# freeDSP.net
KiCad netlist of a schematic drawn in EAGLE
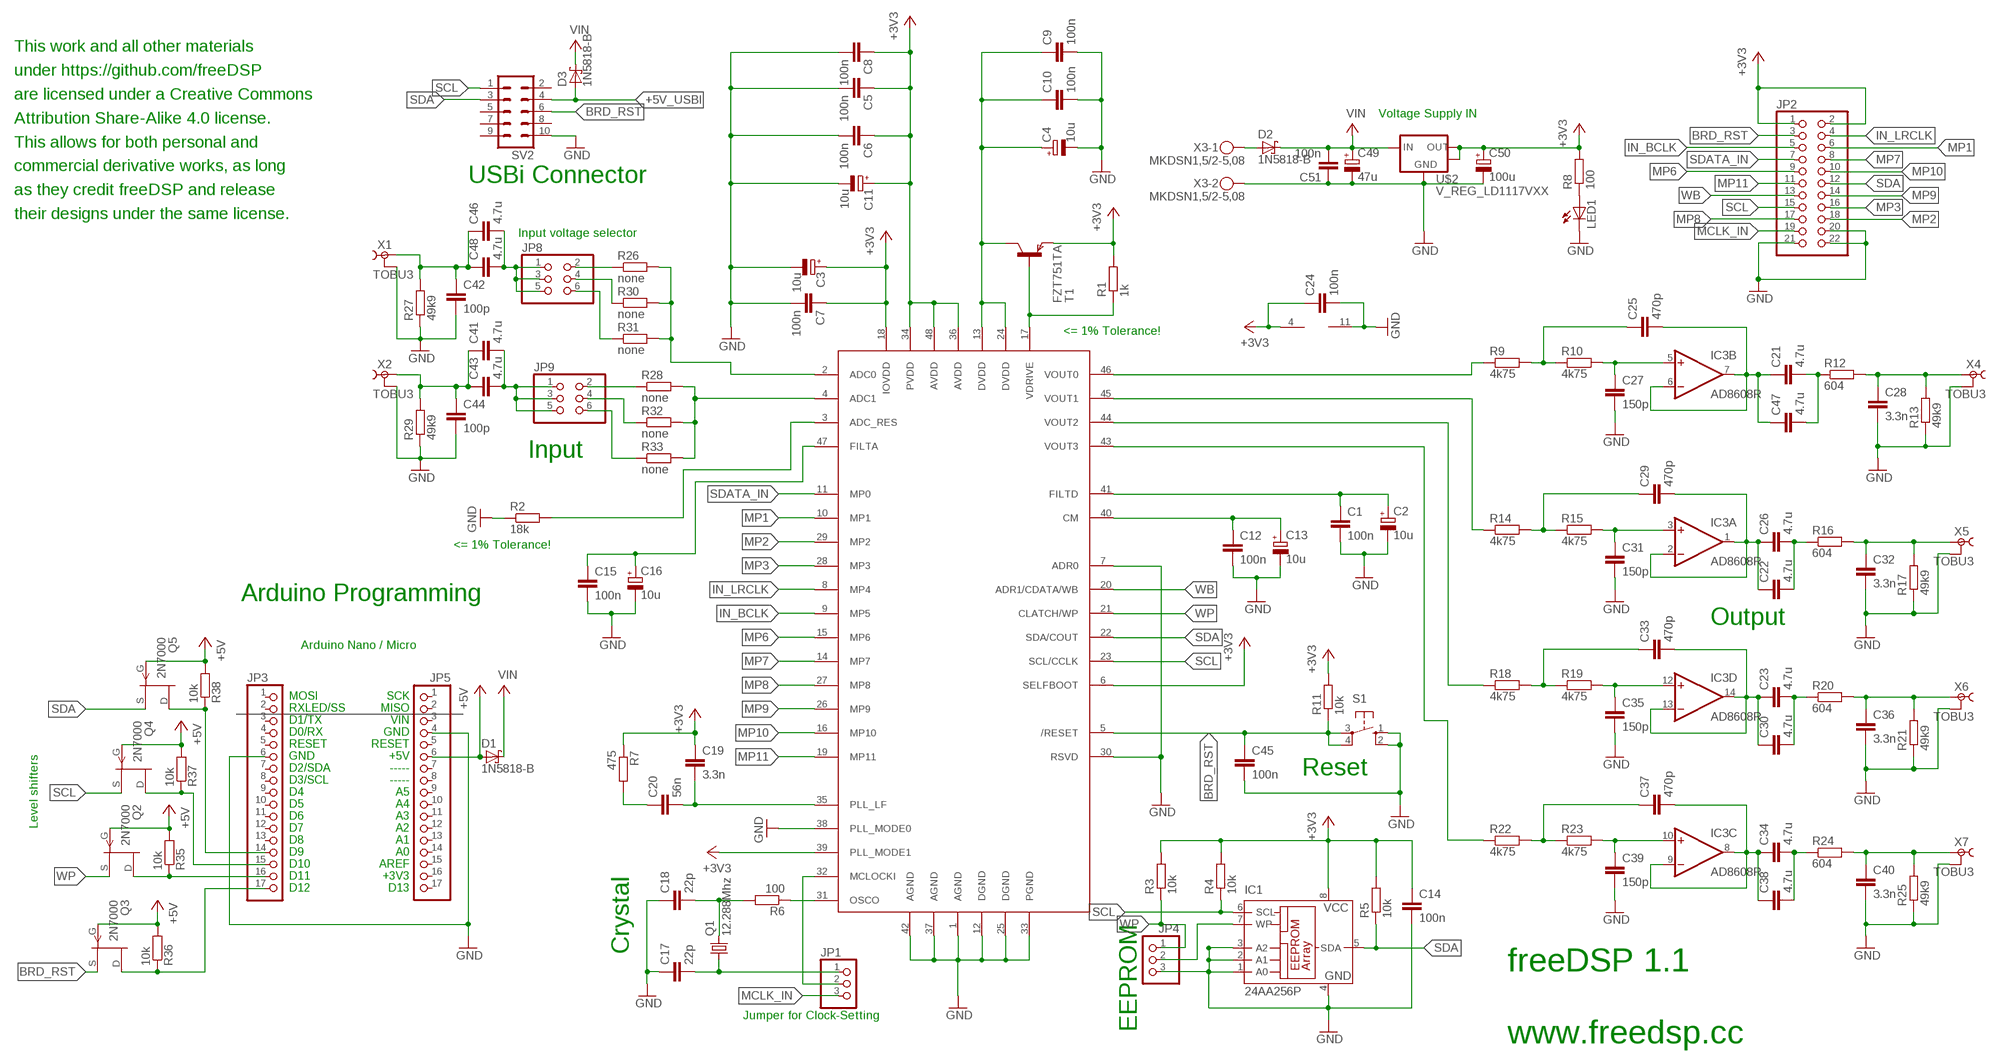
[diagram p0: schematic, sheet 1]

(export (version "E")
  (design (tool "Eeschema 10.0.6"))
  (components
    (comp (ref "C1")
      (value "100n")
      (footprint "eagle-import:C025-025X050")
      (libsource (lib "eagle-import") (part "C-EU025-025X050"))
    )
    (comp (ref "C2")
      (value "10u")
      (footprint "eagle-import:E1,8-4")
      (libsource (lib "eagle-import") (part "CPOL-EUE1.8-4"))
    )
    (comp (ref "C3")
      (value "10u")
      (footprint "eagle-import:E1,8-4")
      (libsource (lib "eagle-import") (part "CPOL-EUE1.8-4"))
    )
    (comp (ref "C4")
      (value "10u")
      (footprint "eagle-import:E1,8-4")
      (libsource (lib "eagle-import") (part "CPOL-EUE1.8-4"))
    )
    (comp (ref "C5")
      (value "100n")
      (footprint "eagle-import:C025-025X050")
      (libsource (lib "eagle-import") (part "C-EU025-025X050"))
    )
    (comp (ref "C6")
      (value "100n")
      (footprint "eagle-import:C025-025X050")
      (libsource (lib "eagle-import") (part "C-EU025-025X050"))
    )
    (comp (ref "C7")
      (value "100n")
      (footprint "eagle-import:C025-025X050")
      (libsource (lib "eagle-import") (part "C-EU025-025X050"))
    )
    (comp (ref "C8")
      (value "100n")
      (footprint "eagle-import:C025-025X050")
      (libsource (lib "eagle-import") (part "C-EU025-025X050"))
    )
    (comp (ref "C9")
      (value "100n")
      (footprint "eagle-import:C025-025X050")
      (libsource (lib "eagle-import") (part "C-EU025-025X050"))
    )
    (comp (ref "C10")
      (value "100n")
      (footprint "eagle-import:C025-025X050")
      (libsource (lib "eagle-import") (part "C-EU025-025X050"))
    )
    (comp (ref "C11")
      (value "10u")
      (footprint "eagle-import:E1,8-4")
      (libsource (lib "eagle-import") (part "CPOL-EUE1.8-4"))
    )
    (comp (ref "C12")
      (value "100n")
      (footprint "eagle-import:C025-025X050")
      (libsource (lib "eagle-import") (part "C-EU025-025X050"))
    )
    (comp (ref "C13")
      (value "10u")
      (footprint "eagle-import:E1,8-4")
      (libsource (lib "eagle-import") (part "CPOL-EUE1.8-4"))
    )
    (comp (ref "C14")
      (value "100n")
      (footprint "eagle-import:C025-025X050")
      (libsource (lib "eagle-import") (part "C-EU025-025X050"))
    )
    (comp (ref "C15")
      (value "100n")
      (footprint "eagle-import:C025-025X050")
      (libsource (lib "eagle-import") (part "C-EU025-025X050"))
    )
    (comp (ref "C16")
      (value "10u")
      (footprint "eagle-import:E1,8-4")
      (libsource (lib "eagle-import") (part "CPOL-EUE1.8-4"))
    )
    (comp (ref "C17")
      (value "22p")
      (footprint "eagle-import:C025-025X050")
      (libsource (lib "eagle-import") (part "C-EU025-025X050"))
    )
    (comp (ref "C18")
      (value "22p")
      (footprint "eagle-import:C025-025X050")
      (libsource (lib "eagle-import") (part "C-EU025-025X050"))
    )
    (comp (ref "C19")
      (value "3.3n")
      (footprint "eagle-import:C025-025X050")
      (libsource (lib "eagle-import") (part "C-EU025-025X050"))
    )
    (comp (ref "C20")
      (value "56n")
      (footprint "eagle-import:C025-025X050")
      (libsource (lib "eagle-import") (part "C-EU025-025X050"))
    )
    (comp (ref "C21")
      (value "4.7u")
      (footprint "eagle-import:C050-075X075")
      (libsource (lib "eagle-import") (part "C-EU050-075X075"))
    )
    (comp (ref "C22")
      (value "4.7u")
      (footprint "eagle-import:C050-075X075")
      (libsource (lib "eagle-import") (part "C-EU050-075X075"))
    )
    (comp (ref "C23")
      (value "4.7u")
      (footprint "eagle-import:C050-075X075")
      (libsource (lib "eagle-import") (part "C-EU050-075X075"))
    )
    (comp (ref "C24")
      (value "100n")
      (footprint "eagle-import:C025-025X050")
      (libsource (lib "eagle-import") (part "C-EU025-025X050"))
    )
    (comp (ref "C25")
      (value "470p")
      (footprint "eagle-import:C050-050X075")
      (libsource (lib "eagle-import") (part "C-EU050-050X075"))
    )
    (comp (ref "C26")
      (value "4.7u")
      (footprint "eagle-import:C050-075X075")
      (libsource (lib "eagle-import") (part "C-EU050-075X075"))
    )
    (comp (ref "C27")
      (value "150p")
      (footprint "eagle-import:C025-025X050")
      (libsource (lib "eagle-import") (part "C-EU025-025X050"))
    )
    (comp (ref "C28")
      (value "3.3n")
      (footprint "eagle-import:C025-025X050")
      (libsource (lib "eagle-import") (part "C-EU025-025X050"))
    )
    (comp (ref "C29")
      (value "470p")
      (footprint "eagle-import:C050-050X075")
      (libsource (lib "eagle-import") (part "C-EU050-050X075"))
    )
    (comp (ref "C30")
      (value "4.7u")
      (footprint "eagle-import:C050-075X075")
      (libsource (lib "eagle-import") (part "C-EU050-075X075"))
    )
    (comp (ref "C31")
      (value "150p")
      (footprint "eagle-import:C025-025X050")
      (libsource (lib "eagle-import") (part "C-EU025-025X050"))
    )
    (comp (ref "C32")
      (value "3.3n")
      (footprint "eagle-import:C025-025X050")
      (libsource (lib "eagle-import") (part "C-EU025-025X050"))
    )
    (comp (ref "C33")
      (value "470p")
      (footprint "eagle-import:C050-050X075")
      (libsource (lib "eagle-import") (part "C-EU050-050X075"))
    )
    (comp (ref "C34")
      (value "4.7u")
      (footprint "eagle-import:C050-075X075")
      (libsource (lib "eagle-import") (part "C-EU050-075X075"))
    )
    (comp (ref "C35")
      (value "150p")
      (footprint "eagle-import:C025-025X050")
      (libsource (lib "eagle-import") (part "C-EU025-025X050"))
    )
    (comp (ref "C36")
      (value "3.3n")
      (footprint "eagle-import:C025-025X050")
      (libsource (lib "eagle-import") (part "C-EU025-025X050"))
    )
    (comp (ref "C37")
      (value "470p")
      (footprint "eagle-import:C050-050X075")
      (libsource (lib "eagle-import") (part "C-EU050-050X075"))
    )
    (comp (ref "C38")
      (value "4.7u")
      (footprint "eagle-import:C050-075X075")
      (libsource (lib "eagle-import") (part "C-EU050-075X075"))
    )
    (comp (ref "C39")
      (value "150p")
      (footprint "eagle-import:C025-025X050")
      (libsource (lib "eagle-import") (part "C-EU025-025X050"))
    )
    (comp (ref "C40")
      (value "3.3n")
      (footprint "eagle-import:C025-025X050")
      (libsource (lib "eagle-import") (part "C-EU025-025X050"))
    )
    (comp (ref "C41")
      (value "4.7u")
      (footprint "eagle-import:C050-075X075")
      (libsource (lib "eagle-import") (part "C-EU050-075X075"))
    )
    (comp (ref "C42")
      (value "100p")
      (footprint "eagle-import:C025-025X050")
      (libsource (lib "eagle-import") (part "C-EU025-025X050"))
    )
    (comp (ref "C43")
      (value "4.7u")
      (footprint "eagle-import:C050-075X075")
      (libsource (lib "eagle-import") (part "C-EU050-075X075"))
    )
    (comp (ref "C44")
      (value "100p")
      (footprint "eagle-import:C025-025X050")
      (libsource (lib "eagle-import") (part "C-EU025-025X050"))
    )
    (comp (ref "C45")
      (value "100n")
      (footprint "eagle-import:C025-025X050")
      (libsource (lib "eagle-import") (part "C-EU025-025X050"))
    )
    (comp (ref "C46")
      (value "4.7u")
      (footprint "eagle-import:C050-075X075")
      (libsource (lib "eagle-import") (part "C-EU050-075X075"))
    )
    (comp (ref "C47")
      (value "4.7u")
      (footprint "eagle-import:C050-075X075")
      (libsource (lib "eagle-import") (part "C-EU050-075X075"))
    )
    (comp (ref "C48")
      (value "4.7u")
      (footprint "eagle-import:C050-075X075")
      (libsource (lib "eagle-import") (part "C-EU050-075X075"))
    )
    (comp (ref "C49")
      (value "47u")
      (footprint "eagle-import:E2,5-6")
      (libsource (lib "eagle-import") (part "CPOL-EUE2.5-6"))
    )
    (comp (ref "C50")
      (value "100u")
      (footprint "eagle-import:E2,5-6")
      (libsource (lib "eagle-import") (part "CPOL-EUE2.5-6"))
    )
    (comp (ref "C51")
      (value "100n")
      (footprint "eagle-import:C025-025X050")
      (libsource (lib "eagle-import") (part "C-EU025-025X050"))
    )
    (comp (ref "D1")
      (value "1N5818-B")
      (footprint "eagle-import:DO41-7.6")
      (libsource (lib "eagle-import") (part "1N5818-B"))
    )
    (comp (ref "D2")
      (value "1N5818-B")
      (footprint "eagle-import:DO41-7.6")
      (libsource (lib "eagle-import") (part "1N5818-B"))
    )
    (comp (ref "D3")
      (value "1N5818-B")
      (footprint "eagle-import:DO41-7.6")
      (libsource (lib "eagle-import") (part "1N5818-B"))
    )
    (comp (ref "IC1")
      (value "24AA256P")
      (footprint "eagle-import:DIL8")
      (fields (field (name "MF") "MICROCHIP") (field (name "MPN") "24AA256-I/P"))
      (libsource (lib "eagle-import") (part "24PAA256"))
    )
    (comp (ref "IC3")
      (value "AD8608R")
      (footprint "eagle-import:SO-14")
      (libsource (lib "eagle-import") (part "AD8608R"))
    )
    (comp (ref "JP1")
      (value "PINHD-1X3")
      (footprint "eagle-import:1X03")
      (libsource (lib "eagle-import") (part "PINHD-1X3"))
    )
    (comp (ref "JP2")
      (value "PINHD-2X11")
      (footprint "eagle-import:2X11")
      (libsource (lib "eagle-import") (part "PINHD-2X11"))
    )
    (comp (ref "JP3")
      (value "PINHD-1X17")
      (footprint "eagle-import:1X17")
      (libsource (lib "eagle-import") (part "PINHD-1X17"))
    )
    (comp (ref "JP4")
      (value "PINHD-1X3")
      (footprint "eagle-import:1X03")
      (libsource (lib "eagle-import") (part "PINHD-1X3"))
    )
    (comp (ref "JP5")
      (value "PINHD-1X17")
      (footprint "eagle-import:1X17")
      (libsource (lib "eagle-import") (part "PINHD-1X17"))
    )
    (comp (ref "JP8")
      (value "PINHD-2X3")
      (footprint "eagle-import:2X03")
      (libsource (lib "eagle-import") (part "PINHD-2X3"))
    )
    (comp (ref "JP9")
      (value "PINHD-2X3")
      (footprint "eagle-import:2X03")
      (libsource (lib "eagle-import") (part "PINHD-2X3"))
    )
    (comp (ref "LED1")
      (value "LED3MM")
      (footprint "eagle-import:LED3MM")
      (libsource (lib "eagle-import") (part "LED3MM"))
    )
    (comp (ref "Q1")
      (value "12.288Mhz")
      (footprint "eagle-import:HC49_S")
      (libsource (lib "eagle-import") (part "CRYSTALHC49S"))
    )
    (comp (ref "Q2")
      (value "2N7000")
      (footprint "eagle-import:TO92")
      (libsource (lib "eagle-import") (part "2N3819"))
    )
    (comp (ref "Q3")
      (value "2N7000")
      (footprint "eagle-import:TO92")
      (libsource (lib "eagle-import") (part "2N3819"))
    )
    (comp (ref "Q4")
      (value "2N7000")
      (footprint "eagle-import:TO92")
      (libsource (lib "eagle-import") (part "2N3819"))
    )
    (comp (ref "Q5")
      (value "2N7000")
      (footprint "eagle-import:TO92")
      (libsource (lib "eagle-import") (part "2N3819"))
    )
    (comp (ref "R1")
      (value "1k")
      (footprint "eagle-import:0207_10")
      (libsource (lib "eagle-import") (part "R-EU_0207/10"))
    )
    (comp (ref "R2")
      (value "18k")
      (footprint "eagle-import:0207_10")
      (libsource (lib "eagle-import") (part "R-EU_0207/10"))
    )
    (comp (ref "R3")
      (value "10k")
      (footprint "eagle-import:0207_10")
      (libsource (lib "eagle-import") (part "R-EU_0207/10"))
    )
    (comp (ref "R4")
      (value "10k")
      (footprint "eagle-import:0207_10")
      (libsource (lib "eagle-import") (part "R-EU_0207/10"))
    )
    (comp (ref "R5")
      (value "10k")
      (footprint "eagle-import:0207_10")
      (libsource (lib "eagle-import") (part "R-EU_0207/10"))
    )
    (comp (ref "R6")
      (value "100")
      (footprint "eagle-import:0207_10")
      (libsource (lib "eagle-import") (part "R-EU_0207/10"))
    )
    (comp (ref "R7")
      (value "475")
      (footprint "eagle-import:0207_10")
      (libsource (lib "eagle-import") (part "R-EU_0207/10"))
    )
    (comp (ref "R8")
      (value "100")
      (footprint "eagle-import:0207_10")
      (libsource (lib "eagle-import") (part "R-EU_0207/10"))
    )
    (comp (ref "R9")
      (value "4k75")
      (footprint "eagle-import:0207_10")
      (libsource (lib "eagle-import") (part "R-EU_0207/10"))
    )
    (comp (ref "R10")
      (value "4k75")
      (footprint "eagle-import:0207_10")
      (libsource (lib "eagle-import") (part "R-EU_0207/10"))
    )
    (comp (ref "R11")
      (value "10k")
      (footprint "eagle-import:0207_10")
      (libsource (lib "eagle-import") (part "R-EU_0207/10"))
    )
    (comp (ref "R12")
      (value "604")
      (footprint "eagle-import:0207_10")
      (libsource (lib "eagle-import") (part "R-EU_0207/10"))
    )
    (comp (ref "R13")
      (value "49k9")
      (footprint "eagle-import:0207_10")
      (libsource (lib "eagle-import") (part "R-EU_0207/10"))
    )
    (comp (ref "R14")
      (value "4k75")
      (footprint "eagle-import:0207_10")
      (libsource (lib "eagle-import") (part "R-EU_0207/10"))
    )
    (comp (ref "R15")
      (value "4k75")
      (footprint "eagle-import:0207_10")
      (libsource (lib "eagle-import") (part "R-EU_0207/10"))
    )
    (comp (ref "R16")
      (value "604")
      (footprint "eagle-import:0207_10")
      (libsource (lib "eagle-import") (part "R-EU_0207/10"))
    )
    (comp (ref "R17")
      (value "49k9")
      (footprint "eagle-import:0207_10")
      (libsource (lib "eagle-import") (part "R-EU_0207/10"))
    )
    (comp (ref "R18")
      (value "4k75")
      (footprint "eagle-import:0207_10")
      (libsource (lib "eagle-import") (part "R-EU_0207/10"))
    )
    (comp (ref "R19")
      (value "4k75")
      (footprint "eagle-import:0207_10")
      (libsource (lib "eagle-import") (part "R-EU_0207/10"))
    )
    (comp (ref "R20")
      (value "604")
      (footprint "eagle-import:0207_10")
      (libsource (lib "eagle-import") (part "R-EU_0207/10"))
    )
    (comp (ref "R21")
      (value "49k9")
      (footprint "eagle-import:0207_10")
      (libsource (lib "eagle-import") (part "R-EU_0207/10"))
    )
    (comp (ref "R22")
      (value "4k75")
      (footprint "eagle-import:0207_10")
      (libsource (lib "eagle-import") (part "R-EU_0207/10"))
    )
    (comp (ref "R23")
      (value "4k75")
      (footprint "eagle-import:0207_10")
      (libsource (lib "eagle-import") (part "R-EU_0207/10"))
    )
    (comp (ref "R24")
      (value "604")
      (footprint "eagle-import:0207_10")
      (libsource (lib "eagle-import") (part "R-EU_0207/10"))
    )
    (comp (ref "R25")
      (value "49k9")
      (footprint "eagle-import:0207_10")
      (libsource (lib "eagle-import") (part "R-EU_0207/10"))
    )
    (comp (ref "R26")
      (value "none")
      (footprint "eagle-import:0207_10")
      (libsource (lib "eagle-import") (part "R-EU_0207/10"))
    )
    (comp (ref "R27")
      (value "49k9")
      (footprint "eagle-import:0207_10")
      (libsource (lib "eagle-import") (part "R-EU_0207/10"))
    )
    (comp (ref "R28")
      (value "none")
      (footprint "eagle-import:0207_10")
      (libsource (lib "eagle-import") (part "R-EU_0207/10"))
    )
    (comp (ref "R29")
      (value "49k9")
      (footprint "eagle-import:0207_10")
      (libsource (lib "eagle-import") (part "R-EU_0207/10"))
    )
    (comp (ref "R30")
      (value "none")
      (footprint "eagle-import:0207_10")
      (libsource (lib "eagle-import") (part "R-EU_0207/10"))
    )
    (comp (ref "R31")
      (value "none")
      (footprint "eagle-import:0207_10")
      (libsource (lib "eagle-import") (part "R-EU_0207/10"))
    )
    (comp (ref "R32")
      (value "none")
      (footprint "eagle-import:0207_10")
      (libsource (lib "eagle-import") (part "R-EU_0207/10"))
    )
    (comp (ref "R33")
      (value "none")
      (footprint "eagle-import:0207_10")
      (libsource (lib "eagle-import") (part "R-EU_0207/10"))
    )
    (comp (ref "R35")
      (value "10k")
      (footprint "eagle-import:0207_10")
      (libsource (lib "eagle-import") (part "R-EU_0207/10"))
    )
    (comp (ref "R36")
      (value "10k")
      (footprint "eagle-import:0207_10")
      (libsource (lib "eagle-import") (part "R-EU_0207/10"))
    )
    (comp (ref "R37")
      (value "10k")
      (footprint "eagle-import:0207_10")
      (libsource (lib "eagle-import") (part "R-EU_0207/10"))
    )
    (comp (ref "R38")
      (value "10k")
      (footprint "eagle-import:0207_10")
      (libsource (lib "eagle-import") (part "R-EU_0207/10"))
    )
    (comp (ref "S1")
      (value "10-XX")
      (footprint "eagle-import:B3F-10XX")
      (fields (field (name "MPN") "B3F-1000"))
      (libsource (lib "eagle-import") (part "10-XX"))
    )
    (comp (ref "SV2")
      (value "ML10")
      (footprint "eagle-import:ML10")
      (libsource (lib "eagle-import") (part "ML10"))
    )
    (comp (ref "T1")
      (value "FZT751TA")
      (footprint "eagle-import:SOT223")
      (fields (field (name "MPN") "FZT789A"))
      (libsource (lib "eagle-import") (part "FZT789A"))
    )
    (comp (ref "U$1")
      (value "ADAU1701")
      (footprint "eagle-import:LQFP-48")
      (libsource (lib "eagle-import") (part "ADAU1701"))
    )
    (comp (ref "U$2")
      (value "V_REG_LD1117VXX")
      (footprint "eagle-import:78XXL")
      (libsource (lib "eagle-import") (part "V_REG_LD1117VXX"))
    )
    (comp (ref "X1")
      (value "TOBU3")
      (footprint "eagle-import:TOBU3")
      (fields (field (name "MF") "FARNELL") (field (name "MPN") "TOBU 3"))
      (libsource (lib "eagle-import") (part "TOBU3"))
    )
    (comp (ref "X2")
      (value "TOBU3")
      (footprint "eagle-import:TOBU3")
      (fields (field (name "MF") "FARNELL") (field (name "MPN") "TOBU 3"))
      (libsource (lib "eagle-import") (part "TOBU3"))
    )
    (comp (ref "X3")
      (value "MKDSN1,5/2-5,08")
      (footprint "eagle-import:MKDSN1,5_2-5,08")
      (fields (field (name "MPN") "MKDSN 1,5/2-5.08"))
      (libsource (lib "eagle-import") (part "MKDSN1,5/2-5,08"))
    )
    (comp (ref "X4")
      (value "TOBU3")
      (footprint "eagle-import:TOBU3")
      (fields (field (name "MF") "FARNELL") (field (name "MPN") "TOBU 3"))
      (libsource (lib "eagle-import") (part "TOBU3"))
    )
    (comp (ref "X5")
      (value "TOBU3")
      (footprint "eagle-import:TOBU3")
      (fields (field (name "MF") "FARNELL") (field (name "MPN") "TOBU 3"))
      (libsource (lib "eagle-import") (part "TOBU3"))
    )
    (comp (ref "X6")
      (value "TOBU3")
      (footprint "eagle-import:TOBU3")
      (fields (field (name "MF") "FARNELL") (field (name "MPN") "TOBU 3"))
      (libsource (lib "eagle-import") (part "TOBU3"))
    )
    (comp (ref "X7")
      (value "TOBU3")
      (footprint "eagle-import:TOBU3")
      (fields (field (name "MF") "FARNELL") (field (name "MPN") "TOBU 3"))
      (libsource (lib "eagle-import") (part "TOBU3"))
    )
  )
  (nets
    (net (code "1") (name "+3V3") (class "Default")
      (node (ref "C11") (pin "+") (pinfunction "+_+") (pintype "passive"))
      (node (ref "C14") (pin "1") (pinfunction "1_1") (pintype "passive"))
      (node (ref "C19") (pin "1") (pinfunction "1_1") (pintype "passive"))
      (node (ref "C24") (pin "1") (pinfunction "1_1") (pintype "passive"))
      (node (ref "C3") (pin "+") (pinfunction "+_+") (pintype "passive"))
      (node (ref "C5") (pin "1") (pinfunction "1_1") (pintype "passive"))
      (node (ref "C50") (pin "+") (pinfunction "+_+") (pintype "passive"))
      (node (ref "C6") (pin "1") (pinfunction "1_1") (pintype "passive"))
      (node (ref "C7") (pin "1") (pinfunction "1_1") (pintype "passive"))
      (node (ref "C8") (pin "1") (pinfunction "1_1") (pintype "passive"))
      (node (ref "IC1") (pin "8") (pinfunction "VCC_8") (pintype "power_in"))
      (node (ref "IC3") (pin "4") (pinfunction "V+_4") (pintype "power_in"))
      (node (ref "JP2") (pin "1") (pinfunction "1_1") (pintype "passive"))
      (node (ref "JP2") (pin "2") (pinfunction "2_2") (pintype "passive"))
      (node (ref "R1") (pin "2") (pinfunction "2_2") (pintype "passive"))
      (node (ref "R11") (pin "2") (pinfunction "2_2") (pintype "passive"))
      (node (ref "R3") (pin "2") (pinfunction "2_2") (pintype "passive"))
      (node (ref "R4") (pin "2") (pinfunction "2_2") (pintype "passive"))
      (node (ref "R5") (pin "2") (pinfunction "2_2") (pintype "passive"))
      (node (ref "R7") (pin "1") (pinfunction "1_1") (pintype "passive"))
      (node (ref "R8") (pin "2") (pinfunction "2_2") (pintype "passive"))
      (node (ref "T1") (pin "3") (pinfunction "E_3") (pintype "passive"))
      (node (ref "U$1") (pin "18") (pinfunction "IOVDD_18") (pintype "bidirectional"))
      (node (ref "U$1") (pin "34") (pinfunction "PVDD_34") (pintype "bidirectional"))
      (node (ref "U$1") (pin "36") (pinfunction "AVDD_36") (pintype "bidirectional"))
      (node (ref "U$1") (pin "39") (pinfunction "PLL_MODE1_39") (pintype "bidirectional"))
      (node (ref "U$1") (pin "48") (pinfunction "AVDD_48") (pintype "bidirectional"))
      (node (ref "U$1") (pin "6") (pinfunction "SELFBOOT_6") (pintype "bidirectional"))
      (node (ref "U$2") (pin "GND") (pinfunction "OUT_GND") (pintype "output"))
      (node (ref "U$2") (pin "OUT2") (pinfunction "OUT2_OUT2") (pintype "output"))
    )
    (net (code "2") (name "+5V") (class "Default")
      (node (ref "D1") (pin "A") (pinfunction "A_A") (pintype "passive"))
      (node (ref "JP5") (pin "6") (pinfunction "6_6") (pintype "passive"))
      (node (ref "Q2") (pin "2") (pinfunction "G_2") (pintype "passive"))
      (node (ref "Q3") (pin "2") (pinfunction "G_2") (pintype "passive"))
      (node (ref "Q4") (pin "2") (pinfunction "G_2") (pintype "passive"))
      (node (ref "Q5") (pin "2") (pinfunction "G_2") (pintype "passive"))
      (node (ref "R35") (pin "2") (pinfunction "2_2") (pintype "passive"))
      (node (ref "R36") (pin "2") (pinfunction "2_2") (pintype "passive"))
      (node (ref "R37") (pin "2") (pinfunction "2_2") (pintype "passive"))
      (node (ref "R38") (pin "2") (pinfunction "2_2") (pintype "passive"))
    )
    (net (code "3") (name "+5V_USBI") (class "Default")
      (node (ref "D3") (pin "A") (pinfunction "A_A") (pintype "passive"))
      (node (ref "SV2") (pin "4") (pinfunction "4_4") (pintype "passive"))
    )
    (net (code "4") (name "BRD_RST") (class "Default")
      (node (ref "C45") (pin "1") (pinfunction "1_1") (pintype "passive"))
      (node (ref "JP2") (pin "3") (pinfunction "3_3") (pintype "passive"))
      (node (ref "Q3") (pin "3") (pinfunction "S_3") (pintype "passive"))
      (node (ref "R11") (pin "1") (pinfunction "1_1") (pintype "passive"))
      (node (ref "S1") (pin "3") (pinfunction "P_3") (pintype "passive"))
      (node (ref "S1") (pin "4") (pinfunction "P1_4") (pintype "passive"))
      (node (ref "SV2") (pin "6") (pinfunction "6_6") (pintype "passive"))
      (node (ref "U$1") (pin "5") (pinfunction "/RESET_5") (pintype "bidirectional"))
    )
    (net (code "5") (name "GND") (class "Default")
      (node (ref "C1") (pin "2") (pinfunction "2_2") (pintype "passive"))
      (node (ref "C10") (pin "2") (pinfunction "2_2") (pintype "passive"))
      (node (ref "C11") (pin "-") (pinfunction "-_-") (pintype "passive"))
      (node (ref "C12") (pin "2") (pinfunction "2_2") (pintype "passive"))
      (node (ref "C13") (pin "-") (pinfunction "-_-") (pintype "passive"))
      (node (ref "C14") (pin "2") (pinfunction "2_2") (pintype "passive"))
      (node (ref "C15") (pin "2") (pinfunction "2_2") (pintype "passive"))
      (node (ref "C16") (pin "-") (pinfunction "-_-") (pintype "passive"))
      (node (ref "C17") (pin "1") (pinfunction "1_1") (pintype "passive"))
      (node (ref "C18") (pin "1") (pinfunction "1_1") (pintype "passive"))
      (node (ref "C2") (pin "-") (pinfunction "-_-") (pintype "passive"))
      (node (ref "C24") (pin "2") (pinfunction "2_2") (pintype "passive"))
      (node (ref "C27") (pin "2") (pinfunction "2_2") (pintype "passive"))
      (node (ref "C28") (pin "2") (pinfunction "2_2") (pintype "passive"))
      (node (ref "C3") (pin "-") (pinfunction "-_-") (pintype "passive"))
      (node (ref "C31") (pin "2") (pinfunction "2_2") (pintype "passive"))
      (node (ref "C32") (pin "2") (pinfunction "2_2") (pintype "passive"))
      (node (ref "C35") (pin "2") (pinfunction "2_2") (pintype "passive"))
      (node (ref "C36") (pin "2") (pinfunction "2_2") (pintype "passive"))
      (node (ref "C39") (pin "2") (pinfunction "2_2") (pintype "passive"))
      (node (ref "C4") (pin "-") (pinfunction "-_-") (pintype "passive"))
      (node (ref "C40") (pin "2") (pinfunction "2_2") (pintype "passive"))
      (node (ref "C42") (pin "2") (pinfunction "2_2") (pintype "passive"))
      (node (ref "C44") (pin "2") (pinfunction "2_2") (pintype "passive"))
      (node (ref "C45") (pin "2") (pinfunction "2_2") (pintype "passive"))
      (node (ref "C49") (pin "-") (pinfunction "-_-") (pintype "passive"))
      (node (ref "C5") (pin "2") (pinfunction "2_2") (pintype "passive"))
      (node (ref "C50") (pin "-") (pinfunction "-_-") (pintype "passive"))
      (node (ref "C51") (pin "1") (pinfunction "1_1") (pintype "passive"))
      (node (ref "C6") (pin "2") (pinfunction "2_2") (pintype "passive"))
      (node (ref "C7") (pin "2") (pinfunction "2_2") (pintype "passive"))
      (node (ref "C8") (pin "2") (pinfunction "2_2") (pintype "passive"))
      (node (ref "C9") (pin "2") (pinfunction "2_2") (pintype "passive"))
      (node (ref "IC1") (pin "1") (pinfunction "A0_1") (pintype "input"))
      (node (ref "IC1") (pin "2") (pinfunction "A1_2") (pintype "input"))
      (node (ref "IC1") (pin "3") (pinfunction "A2_3") (pintype "input"))
      (node (ref "IC1") (pin "4") (pinfunction "GND_4") (pintype "power_in"))
      (node (ref "IC3") (pin "11") (pinfunction "V-_11") (pintype "power_in"))
      (node (ref "JP2") (pin "20") (pinfunction "20_20") (pintype "passive"))
      (node (ref "JP2") (pin "21") (pinfunction "21_21") (pintype "passive"))
      (node (ref "JP2") (pin "22") (pinfunction "22_22") (pintype "passive"))
      (node (ref "JP3") (pin "6") (pinfunction "6_6") (pintype "passive"))
      (node (ref "JP4") (pin "3") (pinfunction "3_3") (pintype "passive"))
      (node (ref "JP5") (pin "4") (pinfunction "4_4") (pintype "passive"))
      (node (ref "LED1") (pin "K") (pinfunction "C_K") (pintype "passive"))
      (node (ref "R13") (pin "1") (pinfunction "1_1") (pintype "passive"))
      (node (ref "R17") (pin "1") (pinfunction "1_1") (pintype "passive"))
      (node (ref "R2") (pin "1") (pinfunction "1_1") (pintype "passive"))
      (node (ref "R21") (pin "1") (pinfunction "1_1") (pintype "passive"))
      (node (ref "R25") (pin "1") (pinfunction "1_1") (pintype "passive"))
      (node (ref "R27") (pin "1") (pinfunction "1_1") (pintype "passive"))
      (node (ref "R29") (pin "1") (pinfunction "1_1") (pintype "passive"))
      (node (ref "S1") (pin "1") (pinfunction "S_1") (pintype "passive"))
      (node (ref "S1") (pin "2") (pinfunction "S1_2") (pintype "passive"))
      (node (ref "SV2") (pin "10") (pinfunction "10_10") (pintype "passive"))
      (node (ref "U$1") (pin "1") (pinfunction "AGND_1") (pintype "bidirectional"))
      (node (ref "U$1") (pin "12") (pinfunction "DGND_12") (pintype "bidirectional"))
      (node (ref "U$1") (pin "25") (pinfunction "DGND_25") (pintype "bidirectional"))
      (node (ref "U$1") (pin "30") (pinfunction "RSVD_30") (pintype "bidirectional"))
      (node (ref "U$1") (pin "33") (pinfunction "PGND_33") (pintype "bidirectional"))
      (node (ref "U$1") (pin "37") (pinfunction "AGND_37") (pintype "bidirectional"))
      (node (ref "U$1") (pin "38") (pinfunction "PLL_MODE0_38") (pintype "bidirectional"))
      (node (ref "U$1") (pin "42") (pinfunction "AGND_42") (pintype "bidirectional"))
      (node (ref "U$1") (pin "7") (pinfunction "ADR0_7") (pintype "bidirectional"))
      (node (ref "U$2") (pin "IN") (pinfunction "GND_IN") (pintype "input"))
      (node (ref "X1") (pin "2") (pinfunction "2_2") (pintype "passive"))
      (node (ref "X1") (pin "2@1") (pinfunction "2_2@1") (pintype "passive"))
      (node (ref "X1") (pin "2@2") (pinfunction "2_2@2") (pintype "passive"))
      (node (ref "X2") (pin "2") (pinfunction "2_2") (pintype "passive"))
      (node (ref "X2") (pin "2@1") (pinfunction "2_2@1") (pintype "passive"))
      (node (ref "X2") (pin "2@2") (pinfunction "2_2@2") (pintype "passive"))
      (node (ref "X3") (pin "2") (pinfunction "KL_2") (pintype "passive"))
      (node (ref "X4") (pin "2") (pinfunction "2_2") (pintype "passive"))
      (node (ref "X4") (pin "2@1") (pinfunction "2_2@1") (pintype "passive"))
      (node (ref "X4") (pin "2@2") (pinfunction "2_2@2") (pintype "passive"))
      (node (ref "X5") (pin "2") (pinfunction "2_2") (pintype "passive"))
      (node (ref "X5") (pin "2@1") (pinfunction "2_2@1") (pintype "passive"))
      (node (ref "X5") (pin "2@2") (pinfunction "2_2@2") (pintype "passive"))
      (node (ref "X6") (pin "2") (pinfunction "2_2") (pintype "passive"))
      (node (ref "X6") (pin "2@1") (pinfunction "2_2@1") (pintype "passive"))
      (node (ref "X6") (pin "2@2") (pinfunction "2_2@2") (pintype "passive"))
      (node (ref "X7") (pin "2") (pinfunction "2_2") (pintype "passive"))
      (node (ref "X7") (pin "2@1") (pinfunction "2_2@1") (pintype "passive"))
      (node (ref "X7") (pin "2@2") (pinfunction "2_2@2") (pintype "passive"))
    )
    (net (code "6") (name "IN_BCLK") (class "Default")
      (node (ref "JP2") (pin "5") (pinfunction "5_5") (pintype "passive"))
      (node (ref "U$1") (pin "9") (pinfunction "MP5_9") (pintype "bidirectional"))
    )
    (net (code "7") (name "IN_LRCLK") (class "Default")
      (node (ref "JP2") (pin "4") (pinfunction "4_4") (pintype "passive"))
      (node (ref "U$1") (pin "8") (pinfunction "MP4_8") (pintype "bidirectional"))
    )
    (net (code "8") (name "MCLK_IN") (class "Default")
      (node (ref "JP1") (pin "3") (pinfunction "3_3") (pintype "passive"))
      (node (ref "JP2") (pin "19") (pinfunction "19_19") (pintype "passive"))
    )
    (net (code "9") (name "MP1") (class "Default")
      (node (ref "JP2") (pin "6") (pinfunction "6_6") (pintype "passive"))
      (node (ref "U$1") (pin "10") (pinfunction "MP1_10") (pintype "bidirectional"))
    )
    (net (code "10") (name "MP2") (class "Default")
      (node (ref "JP2") (pin "18") (pinfunction "18_18") (pintype "passive"))
      (node (ref "U$1") (pin "29") (pinfunction "MP2_29") (pintype "bidirectional"))
    )
    (net (code "11") (name "MP3") (class "Default")
      (node (ref "JP2") (pin "16") (pinfunction "16_16") (pintype "passive"))
      (node (ref "U$1") (pin "28") (pinfunction "MP3_28") (pintype "bidirectional"))
    )
    (net (code "12") (name "MP6") (class "Default")
      (node (ref "JP2") (pin "9") (pinfunction "9_9") (pintype "passive"))
      (node (ref "U$1") (pin "15") (pinfunction "MP6_15") (pintype "bidirectional"))
    )
    (net (code "13") (name "MP7") (class "Default")
      (node (ref "JP2") (pin "8") (pinfunction "8_8") (pintype "passive"))
      (node (ref "U$1") (pin "14") (pinfunction "MP7_14") (pintype "bidirectional"))
    )
    (net (code "14") (name "MP8") (class "Default")
      (node (ref "JP2") (pin "17") (pinfunction "17_17") (pintype "passive"))
      (node (ref "U$1") (pin "27") (pinfunction "MP8_27") (pintype "bidirectional"))
    )
    (net (code "15") (name "MP9") (class "Default")
      (node (ref "JP2") (pin "14") (pinfunction "14_14") (pintype "passive"))
      (node (ref "U$1") (pin "26") (pinfunction "MP9_26") (pintype "bidirectional"))
    )
    (net (code "16") (name "MP10") (class "Default")
      (node (ref "JP2") (pin "10") (pinfunction "10_10") (pintype "passive"))
      (node (ref "U$1") (pin "16") (pinfunction "MP10_16") (pintype "bidirectional"))
    )
    (net (code "17") (name "MP11") (class "Default")
      (node (ref "JP2") (pin "11") (pinfunction "11_11") (pintype "passive"))
      (node (ref "U$1") (pin "19") (pinfunction "MP11_19") (pintype "bidirectional"))
    )
    (net (code "18") (name "Net-(C10-Pad1)") (class "Default")
      (node (ref "C10") (pin "1") (pinfunction "1_1") (pintype "passive"))
      (node (ref "C4") (pin "+") (pinfunction "+_+") (pintype "passive"))
      (node (ref "C9") (pin "1") (pinfunction "1_1") (pintype "passive"))
      (node (ref "T1") (pin "2") (pinfunction "C_2") (pintype "passive"))
      (node (ref "T1") (pin "4") (pinfunction "C_4") (pintype "passive"))
      (node (ref "U$1") (pin "13") (pinfunction "DVDD_13") (pintype "bidirectional"))
      (node (ref "U$1") (pin "24") (pinfunction "DVDD_24") (pintype "bidirectional"))
    )
    (net (code "19") (name "Net-(C17-Pad2)") (class "Default")
      (node (ref "C17") (pin "2") (pinfunction "2_2") (pintype "passive"))
      (node (ref "JP1") (pin "1") (pinfunction "1_1") (pintype "passive"))
      (node (ref "Q1") (pin "1") (pinfunction "1_1") (pintype "passive"))
    )
    (net (code "20") (name "Net-(C18-Pad2)") (class "Default")
      (node (ref "C18") (pin "2") (pinfunction "2_2") (pintype "passive"))
      (node (ref "Q1") (pin "2") (pinfunction "2_2") (pintype "passive"))
      (node (ref "R6") (pin "2") (pinfunction "2_2") (pintype "passive"))
    )
    (net (code "21") (name "Net-(C20-Pad1)") (class "Default")
      (node (ref "C20") (pin "1") (pinfunction "1_1") (pintype "passive"))
      (node (ref "R7") (pin "2") (pinfunction "2_2") (pintype "passive"))
    )
    (net (code "22") (name "Net-(C21-Pad2)") (class "Default")
      (node (ref "C21") (pin "2") (pinfunction "2_2") (pintype "passive"))
      (node (ref "C47") (pin "2") (pinfunction "2_2") (pintype "passive"))
      (node (ref "R12") (pin "1") (pinfunction "1_1") (pintype "passive"))
    )
    (net (code "23") (name "Net-(C22-Pad2)") (class "Default")
      (node (ref "C22") (pin "2") (pinfunction "2_2") (pintype "passive"))
      (node (ref "C26") (pin "2") (pinfunction "2_2") (pintype "passive"))
      (node (ref "R16") (pin "1") (pinfunction "1_1") (pintype "passive"))
    )
    (net (code "24") (name "Net-(C23-Pad2)") (class "Default")
      (node (ref "C23") (pin "2") (pinfunction "2_2") (pintype "passive"))
      (node (ref "C30") (pin "2") (pinfunction "2_2") (pintype "passive"))
      (node (ref "R20") (pin "1") (pinfunction "1_1") (pintype "passive"))
    )
    (net (code "25") (name "Net-(C25-Pad1)") (class "Default")
      (node (ref "C25") (pin "1") (pinfunction "1_1") (pintype "passive"))
      (node (ref "R10") (pin "1") (pinfunction "1_1") (pintype "passive"))
      (node (ref "R9") (pin "2") (pinfunction "2_2") (pintype "passive"))
    )
    (net (code "26") (name "Net-(C28-Pad1)") (class "Default")
      (node (ref "C28") (pin "1") (pinfunction "1_1") (pintype "passive"))
      (node (ref "R12") (pin "2") (pinfunction "2_2") (pintype "passive"))
      (node (ref "R13") (pin "2") (pinfunction "2_2") (pintype "passive"))
      (node (ref "X4") (pin "1") (pinfunction "1_1") (pintype "passive"))
    )
    (net (code "27") (name "Net-(C29-Pad1)") (class "Default")
      (node (ref "C29") (pin "1") (pinfunction "1_1") (pintype "passive"))
      (node (ref "R14") (pin "2") (pinfunction "2_2") (pintype "passive"))
      (node (ref "R15") (pin "1") (pinfunction "1_1") (pintype "passive"))
    )
    (net (code "28") (name "Net-(C32-Pad1)") (class "Default")
      (node (ref "C32") (pin "1") (pinfunction "1_1") (pintype "passive"))
      (node (ref "R16") (pin "2") (pinfunction "2_2") (pintype "passive"))
      (node (ref "R17") (pin "2") (pinfunction "2_2") (pintype "passive"))
      (node (ref "X5") (pin "1") (pinfunction "1_1") (pintype "passive"))
    )
    (net (code "29") (name "Net-(C33-Pad1)") (class "Default")
      (node (ref "C33") (pin "1") (pinfunction "1_1") (pintype "passive"))
      (node (ref "R18") (pin "2") (pinfunction "2_2") (pintype "passive"))
      (node (ref "R19") (pin "1") (pinfunction "1_1") (pintype "passive"))
    )
    (net (code "30") (name "Net-(C34-Pad2)") (class "Default")
      (node (ref "C34") (pin "2") (pinfunction "2_2") (pintype "passive"))
      (node (ref "C38") (pin "2") (pinfunction "2_2") (pintype "passive"))
      (node (ref "R24") (pin "1") (pinfunction "1_1") (pintype "passive"))
    )
    (net (code "31") (name "Net-(C36-Pad1)") (class "Default")
      (node (ref "C36") (pin "1") (pinfunction "1_1") (pintype "passive"))
      (node (ref "R20") (pin "2") (pinfunction "2_2") (pintype "passive"))
      (node (ref "R21") (pin "2") (pinfunction "2_2") (pintype "passive"))
      (node (ref "X6") (pin "1") (pinfunction "1_1") (pintype "passive"))
    )
    (net (code "32") (name "Net-(C37-Pad1)") (class "Default")
      (node (ref "C37") (pin "1") (pinfunction "1_1") (pintype "passive"))
      (node (ref "R22") (pin "2") (pinfunction "2_2") (pintype "passive"))
      (node (ref "R23") (pin "1") (pinfunction "1_1") (pintype "passive"))
    )
    (net (code "33") (name "Net-(C40-Pad1)") (class "Default")
      (node (ref "C40") (pin "1") (pinfunction "1_1") (pintype "passive"))
      (node (ref "R24") (pin "2") (pinfunction "2_2") (pintype "passive"))
      (node (ref "R25") (pin "2") (pinfunction "2_2") (pintype "passive"))
      (node (ref "X7") (pin "1") (pinfunction "1_1") (pintype "passive"))
    )
    (net (code "34") (name "Net-(C41-Pad1)") (class "Default")
      (node (ref "C41") (pin "1") (pinfunction "1_1") (pintype "passive"))
      (node (ref "C43") (pin "1") (pinfunction "1_1") (pintype "passive"))
      (node (ref "C44") (pin "1") (pinfunction "1_1") (pintype "passive"))
      (node (ref "R29") (pin "2") (pinfunction "2_2") (pintype "passive"))
      (node (ref "X2") (pin "1") (pinfunction "1_1") (pintype "passive"))
    )
    (net (code "35") (name "Net-(C41-Pad2)") (class "Default")
      (node (ref "C41") (pin "2") (pinfunction "2_2") (pintype "passive"))
      (node (ref "C43") (pin "2") (pinfunction "2_2") (pintype "passive"))
      (node (ref "JP9") (pin "1") (pinfunction "1_1") (pintype "passive"))
      (node (ref "JP9") (pin "3") (pinfunction "3_3") (pintype "passive"))
      (node (ref "JP9") (pin "5") (pinfunction "5_5") (pintype "passive"))
    )
    (net (code "36") (name "Net-(C42-Pad1)") (class "Default")
      (node (ref "C42") (pin "1") (pinfunction "1_1") (pintype "passive"))
      (node (ref "C46") (pin "1") (pinfunction "1_1") (pintype "passive"))
      (node (ref "C48") (pin "1") (pinfunction "1_1") (pintype "passive"))
      (node (ref "R27") (pin "2") (pinfunction "2_2") (pintype "passive"))
      (node (ref "X1") (pin "1") (pinfunction "1_1") (pintype "passive"))
    )
    (net (code "37") (name "Net-(C46-Pad2)") (class "Default")
      (node (ref "C46") (pin "2") (pinfunction "2_2") (pintype "passive"))
      (node (ref "C48") (pin "2") (pinfunction "2_2") (pintype "passive"))
      (node (ref "JP8") (pin "1") (pinfunction "1_1") (pintype "passive"))
      (node (ref "JP8") (pin "3") (pinfunction "3_3") (pintype "passive"))
      (node (ref "JP8") (pin "5") (pinfunction "5_5") (pintype "passive"))
    )
    (net (code "38") (name "Net-(IC1-WP)") (class "Default")
      (node (ref "IC1") (pin "7") (pinfunction "WP_7") (pintype "input"))
      (node (ref "JP4") (pin "2") (pinfunction "2_2") (pintype "passive"))
    )
    (net (code "39") (name "Net-(IC3A-+IN)") (class "Default")
      (node (ref "C31") (pin "1") (pinfunction "1_1") (pintype "passive"))
      (node (ref "IC3") (pin "3") (pinfunction "+IN_3") (pintype "input"))
      (node (ref "R15") (pin "2") (pinfunction "2_2") (pintype "passive"))
    )
    (net (code "40") (name "Net-(IC3A--IN)") (class "Default")
      (node (ref "C22") (pin "1") (pinfunction "1_1") (pintype "passive"))
      (node (ref "C26") (pin "1") (pinfunction "1_1") (pintype "passive"))
      (node (ref "C29") (pin "2") (pinfunction "2_2") (pintype "passive"))
      (node (ref "IC3") (pin "1") (pinfunction "OUT_1") (pintype "output"))
      (node (ref "IC3") (pin "2") (pinfunction "-IN_2") (pintype "input"))
    )
    (net (code "41") (name "Net-(IC3B-+IN)") (class "Default")
      (node (ref "C27") (pin "1") (pinfunction "1_1") (pintype "passive"))
      (node (ref "IC3") (pin "5") (pinfunction "+IN_5") (pintype "input"))
      (node (ref "R10") (pin "2") (pinfunction "2_2") (pintype "passive"))
    )
    (net (code "42") (name "Net-(IC3B--IN)") (class "Default")
      (node (ref "C21") (pin "1") (pinfunction "1_1") (pintype "passive"))
      (node (ref "C25") (pin "2") (pinfunction "2_2") (pintype "passive"))
      (node (ref "C47") (pin "1") (pinfunction "1_1") (pintype "passive"))
      (node (ref "IC3") (pin "6") (pinfunction "-IN_6") (pintype "input"))
      (node (ref "IC3") (pin "7") (pinfunction "OUT_7") (pintype "output"))
    )
    (net (code "43") (name "Net-(IC3C-+IN)") (class "Default")
      (node (ref "C39") (pin "1") (pinfunction "1_1") (pintype "passive"))
      (node (ref "IC3") (pin "10") (pinfunction "+IN_10") (pintype "input"))
      (node (ref "R23") (pin "2") (pinfunction "2_2") (pintype "passive"))
    )
    (net (code "44") (name "Net-(IC3C--IN)") (class "Default")
      (node (ref "C34") (pin "1") (pinfunction "1_1") (pintype "passive"))
      (node (ref "C37") (pin "2") (pinfunction "2_2") (pintype "passive"))
      (node (ref "C38") (pin "1") (pinfunction "1_1") (pintype "passive"))
      (node (ref "IC3") (pin "8") (pinfunction "OUT_8") (pintype "output"))
      (node (ref "IC3") (pin "9") (pinfunction "-IN_9") (pintype "input"))
    )
    (net (code "45") (name "Net-(IC3D-+IN)") (class "Default")
      (node (ref "C35") (pin "1") (pinfunction "1_1") (pintype "passive"))
      (node (ref "IC3") (pin "12") (pinfunction "+IN_12") (pintype "input"))
      (node (ref "R19") (pin "2") (pinfunction "2_2") (pintype "passive"))
    )
    (net (code "46") (name "Net-(IC3D--IN)") (class "Default")
      (node (ref "C23") (pin "1") (pinfunction "1_1") (pintype "passive"))
      (node (ref "C30") (pin "1") (pinfunction "1_1") (pintype "passive"))
      (node (ref "C33") (pin "2") (pinfunction "2_2") (pintype "passive"))
      (node (ref "IC3") (pin "13") (pinfunction "-IN_13") (pintype "input"))
      (node (ref "IC3") (pin "14") (pinfunction "OUT_14") (pintype "output"))
    )
    (net (code "47") (name "Net-(JP8-Pad2)") (class "Default")
      (node (ref "JP8") (pin "2") (pinfunction "2_2") (pintype "passive"))
      (node (ref "R26") (pin "1") (pinfunction "1_1") (pintype "passive"))
    )
    (net (code "48") (name "Net-(JP8-Pad4)") (class "Default")
      (node (ref "JP8") (pin "4") (pinfunction "4_4") (pintype "passive"))
      (node (ref "R30") (pin "1") (pinfunction "1_1") (pintype "passive"))
    )
    (net (code "49") (name "Net-(JP8-Pad6)") (class "Default")
      (node (ref "JP8") (pin "6") (pinfunction "6_6") (pintype "passive"))
      (node (ref "R31") (pin "1") (pinfunction "1_1") (pintype "passive"))
    )
    (net (code "50") (name "Net-(JP9-Pad2)") (class "Default")
      (node (ref "JP9") (pin "2") (pinfunction "2_2") (pintype "passive"))
      (node (ref "R28") (pin "1") (pinfunction "1_1") (pintype "passive"))
    )
    (net (code "51") (name "Net-(JP9-Pad4)") (class "Default")
      (node (ref "JP9") (pin "4") (pinfunction "4_4") (pintype "passive"))
      (node (ref "R32") (pin "1") (pinfunction "1_1") (pintype "passive"))
    )
    (net (code "52") (name "Net-(JP9-Pad6)") (class "Default")
      (node (ref "JP9") (pin "6") (pinfunction "6_6") (pintype "passive"))
      (node (ref "R33") (pin "1") (pinfunction "1_1") (pintype "passive"))
    )
    (net (code "53") (name "Net-(LED1-PadA)") (class "Default")
      (node (ref "LED1") (pin "A") (pinfunction "A_A") (pintype "passive"))
      (node (ref "R8") (pin "1") (pinfunction "1_1") (pintype "passive"))
    )
    (net (code "54") (name "Net-(Q2-D)") (class "Default")
      (node (ref "JP3") (pin "16") (pinfunction "16_16") (pintype "passive"))
      (node (ref "Q2") (pin "1") (pinfunction "D_1") (pintype "passive"))
      (node (ref "R35") (pin "1") (pinfunction "1_1") (pintype "passive"))
    )
    (net (code "55") (name "Net-(Q3-D)") (class "Default")
      (node (ref "JP3") (pin "17") (pinfunction "17_17") (pintype "passive"))
      (node (ref "Q3") (pin "1") (pinfunction "D_1") (pintype "passive"))
      (node (ref "R36") (pin "1") (pinfunction "1_1") (pintype "passive"))
    )
    (net (code "56") (name "Net-(Q4-D)") (class "Default")
      (node (ref "JP3") (pin "15") (pinfunction "15_15") (pintype "passive"))
      (node (ref "Q4") (pin "1") (pinfunction "D_1") (pintype "passive"))
      (node (ref "R37") (pin "1") (pinfunction "1_1") (pintype "passive"))
    )
    (net (code "57") (name "Net-(Q5-D)") (class "Default")
      (node (ref "JP3") (pin "14") (pinfunction "14_14") (pintype "passive"))
      (node (ref "Q5") (pin "1") (pinfunction "D_1") (pintype "passive"))
      (node (ref "R38") (pin "1") (pinfunction "1_1") (pintype "passive"))
    )
    (net (code "58") (name "Net-(T1-B)") (class "Default")
      (node (ref "R1") (pin "1") (pinfunction "1_1") (pintype "passive"))
      (node (ref "T1") (pin "1") (pinfunction "B_1") (pintype "passive"))
      (node (ref "U$1") (pin "17") (pinfunction "VDRIVE_17") (pintype "bidirectional"))
    )
    (net (code "59") (name "Net-(U$1-ADC0)") (class "Default")
      (node (ref "R26") (pin "2") (pinfunction "2_2") (pintype "passive"))
      (node (ref "R30") (pin "2") (pinfunction "2_2") (pintype "passive"))
      (node (ref "R31") (pin "2") (pinfunction "2_2") (pintype "passive"))
      (node (ref "U$1") (pin "2") (pinfunction "ADC0_2") (pintype "bidirectional"))
    )
    (net (code "60") (name "Net-(U$1-ADC1)") (class "Default")
      (node (ref "R28") (pin "2") (pinfunction "2_2") (pintype "passive"))
      (node (ref "R32") (pin "2") (pinfunction "2_2") (pintype "passive"))
      (node (ref "R33") (pin "2") (pinfunction "2_2") (pintype "passive"))
      (node (ref "U$1") (pin "4") (pinfunction "ADC1_4") (pintype "bidirectional"))
    )
    (net (code "61") (name "Net-(U$1-ADC_RES)") (class "Default")
      (node (ref "R2") (pin "2") (pinfunction "2_2") (pintype "passive"))
      (node (ref "U$1") (pin "3") (pinfunction "ADC_RES_3") (pintype "bidirectional"))
    )
    (net (code "62") (name "Net-(U$1-CM)") (class "Default")
      (node (ref "C12") (pin "1") (pinfunction "1_1") (pintype "passive"))
      (node (ref "C13") (pin "+") (pinfunction "+_+") (pintype "passive"))
      (node (ref "U$1") (pin "40") (pinfunction "CM_40") (pintype "bidirectional"))
    )
    (net (code "63") (name "Net-(U$1-FILTA)") (class "Default")
      (node (ref "C15") (pin "1") (pinfunction "1_1") (pintype "passive"))
      (node (ref "C16") (pin "+") (pinfunction "+_+") (pintype "passive"))
      (node (ref "U$1") (pin "47") (pinfunction "FILTA_47") (pintype "bidirectional"))
    )
    (net (code "64") (name "Net-(U$1-FILTD)") (class "Default")
      (node (ref "C1") (pin "1") (pinfunction "1_1") (pintype "passive"))
      (node (ref "C2") (pin "+") (pinfunction "+_+") (pintype "passive"))
      (node (ref "U$1") (pin "41") (pinfunction "FILTD_41") (pintype "bidirectional"))
    )
    (net (code "65") (name "Net-(U$1-MCLOCKI)") (class "Default")
      (node (ref "JP1") (pin "2") (pinfunction "2_2") (pintype "passive"))
      (node (ref "U$1") (pin "32") (pinfunction "MCLOCKI_32") (pintype "bidirectional"))
    )
    (net (code "66") (name "Net-(U$1-OSCO)") (class "Default")
      (node (ref "R6") (pin "1") (pinfunction "1_1") (pintype "passive"))
      (node (ref "U$1") (pin "31") (pinfunction "OSCO_31") (pintype "bidirectional"))
    )
    (net (code "67") (name "Net-(U$1-PLL_LF)") (class "Default")
      (node (ref "C19") (pin "2") (pinfunction "2_2") (pintype "passive"))
      (node (ref "C20") (pin "2") (pinfunction "2_2") (pintype "passive"))
      (node (ref "U$1") (pin "35") (pinfunction "PLL_LF_35") (pintype "bidirectional"))
    )
    (net (code "68") (name "Net-(U$1-VOUT0)") (class "Default")
      (node (ref "R9") (pin "1") (pinfunction "1_1") (pintype "passive"))
      (node (ref "U$1") (pin "46") (pinfunction "VOUT0_46") (pintype "bidirectional"))
    )
    (net (code "69") (name "Net-(U$1-VOUT1)") (class "Default")
      (node (ref "R14") (pin "1") (pinfunction "1_1") (pintype "passive"))
      (node (ref "U$1") (pin "45") (pinfunction "VOUT1_45") (pintype "bidirectional"))
    )
    (net (code "70") (name "Net-(U$1-VOUT2)") (class "Default")
      (node (ref "R18") (pin "1") (pinfunction "1_1") (pintype "passive"))
      (node (ref "U$1") (pin "44") (pinfunction "VOUT2_44") (pintype "bidirectional"))
    )
    (net (code "71") (name "Net-(U$1-VOUT3)") (class "Default")
      (node (ref "R22") (pin "1") (pinfunction "1_1") (pintype "passive"))
      (node (ref "U$1") (pin "43") (pinfunction "VOUT3_43") (pintype "bidirectional"))
    )
    (net (code "72") (name "Net-(X3A-KL)") (class "Default")
      (node (ref "D2") (pin "A") (pinfunction "A_A") (pintype "passive"))
      (node (ref "X3") (pin "1") (pinfunction "KL_1") (pintype "passive"))
    )
    (net (code "73") (name "SCL") (class "Default")
      (node (ref "IC1") (pin "6") (pinfunction "SCL_6") (pintype "input"))
      (node (ref "JP2") (pin "15") (pinfunction "15_15") (pintype "passive"))
      (node (ref "Q4") (pin "3") (pinfunction "S_3") (pintype "passive"))
      (node (ref "R4") (pin "1") (pinfunction "1_1") (pintype "passive"))
      (node (ref "SV2") (pin "1") (pinfunction "1_1") (pintype "passive"))
      (node (ref "U$1") (pin "23") (pinfunction "SCL/CCLK_23") (pintype "bidirectional"))
    )
    (net (code "74") (name "SDA") (class "Default")
      (node (ref "IC1") (pin "5") (pinfunction "SDA_5") (pintype "bidirectional"))
      (node (ref "JP2") (pin "12") (pinfunction "12_12") (pintype "passive"))
      (node (ref "Q5") (pin "3") (pinfunction "S_3") (pintype "passive"))
      (node (ref "R5") (pin "1") (pinfunction "1_1") (pintype "passive"))
      (node (ref "SV2") (pin "3") (pinfunction "3_3") (pintype "passive"))
      (node (ref "U$1") (pin "22") (pinfunction "SDA/COUT_22") (pintype "bidirectional"))
    )
    (net (code "75") (name "SDATA_IN") (class "Default")
      (node (ref "JP2") (pin "7") (pinfunction "7_7") (pintype "passive"))
      (node (ref "U$1") (pin "11") (pinfunction "MP0_11") (pintype "bidirectional"))
    )
    (net (code "76") (name "VIN") (class "Default")
      (node (ref "C49") (pin "+") (pinfunction "+_+") (pintype "passive"))
      (node (ref "C51") (pin "2") (pinfunction "2_2") (pintype "passive"))
      (node (ref "D1") (pin "C") (pinfunction "C_C") (pintype "passive"))
      (node (ref "D2") (pin "C") (pinfunction "C_C") (pintype "passive"))
      (node (ref "D3") (pin "C") (pinfunction "C_C") (pintype "passive"))
      (node (ref "U$2") (pin "OUT") (pinfunction "IN_OUT") (pintype "input"))
    )
    (net (code "77") (name "WB") (class "Default")
      (node (ref "JP2") (pin "13") (pinfunction "13_13") (pintype "passive"))
      (node (ref "U$1") (pin "20") (pinfunction "ADR1/CDATA/WB_20") (pintype "bidirectional"))
    )
    (net (code "78") (name "WP") (class "Default")
      (node (ref "JP4") (pin "1") (pinfunction "1_1") (pintype "passive"))
      (node (ref "Q2") (pin "3") (pinfunction "S_3") (pintype "passive"))
      (node (ref "R3") (pin "1") (pinfunction "1_1") (pintype "passive"))
      (node (ref "U$1") (pin "21") (pinfunction "CLATCH/WP_21") (pintype "bidirectional"))
    )
    (net (code "79") (name "unconnected-(JP3-Pad1)") (class "Default")
      (node (ref "JP3") (pin "1") (pinfunction "1_1") (pintype "passive"))
    )
    (net (code "80") (name "unconnected-(JP3-Pad2)") (class "Default")
      (node (ref "JP3") (pin "2") (pinfunction "2_2") (pintype "passive"))
    )
    (net (code "81") (name "unconnected-(JP3-Pad3)") (class "Default")
      (node (ref "JP3") (pin "3") (pinfunction "3_3") (pintype "passive"))
    )
    (net (code "82") (name "unconnected-(JP3-Pad4)") (class "Default")
      (node (ref "JP3") (pin "4") (pinfunction "4_4") (pintype "passive"))
    )
    (net (code "83") (name "unconnected-(JP3-Pad5)") (class "Default")
      (node (ref "JP3") (pin "5") (pinfunction "5_5") (pintype "passive"))
    )
    (net (code "84") (name "unconnected-(JP3-Pad7)") (class "Default")
      (node (ref "JP3") (pin "7") (pinfunction "7_7") (pintype "passive"))
    )
    (net (code "85") (name "unconnected-(JP3-Pad8)") (class "Default")
      (node (ref "JP3") (pin "8") (pinfunction "8_8") (pintype "passive"))
    )
    (net (code "86") (name "unconnected-(JP3-Pad9)") (class "Default")
      (node (ref "JP3") (pin "9") (pinfunction "9_9") (pintype "passive"))
    )
    (net (code "87") (name "unconnected-(JP3-Pad10)") (class "Default")
      (node (ref "JP3") (pin "10") (pinfunction "10_10") (pintype "passive"))
    )
    (net (code "88") (name "unconnected-(JP3-Pad11)") (class "Default")
      (node (ref "JP3") (pin "11") (pinfunction "11_11") (pintype "passive"))
    )
    (net (code "89") (name "unconnected-(JP3-Pad12)") (class "Default")
      (node (ref "JP3") (pin "12") (pinfunction "12_12") (pintype "passive"))
    )
    (net (code "90") (name "unconnected-(JP3-Pad13)") (class "Default")
      (node (ref "JP3") (pin "13") (pinfunction "13_13") (pintype "passive"))
    )
    (net (code "91") (name "unconnected-(JP5-Pad1)") (class "Default")
      (node (ref "JP5") (pin "1") (pinfunction "1_1") (pintype "passive"))
    )
    (net (code "92") (name "unconnected-(JP5-Pad2)") (class "Default")
      (node (ref "JP5") (pin "2") (pinfunction "2_2") (pintype "passive"))
    )
    (net (code "93") (name "unconnected-(JP5-Pad3)") (class "Default")
      (node (ref "JP5") (pin "3") (pinfunction "3_3") (pintype "passive"))
    )
    (net (code "94") (name "unconnected-(JP5-Pad5)") (class "Default")
      (node (ref "JP5") (pin "5") (pinfunction "5_5") (pintype "passive"))
    )
    (net (code "95") (name "unconnected-(JP5-Pad7)") (class "Default")
      (node (ref "JP5") (pin "7") (pinfunction "7_7") (pintype "passive"))
    )
    (net (code "96") (name "unconnected-(JP5-Pad8)") (class "Default")
      (node (ref "JP5") (pin "8") (pinfunction "8_8") (pintype "passive"))
    )
    (net (code "97") (name "unconnected-(JP5-Pad9)") (class "Default")
      (node (ref "JP5") (pin "9") (pinfunction "9_9") (pintype "passive"))
    )
    (net (code "98") (name "unconnected-(JP5-Pad10)") (class "Default")
      (node (ref "JP5") (pin "10") (pinfunction "10_10") (pintype "passive"))
    )
    (net (code "99") (name "unconnected-(JP5-Pad11)") (class "Default")
      (node (ref "JP5") (pin "11") (pinfunction "11_11") (pintype "passive"))
    )
    (net (code "100") (name "unconnected-(JP5-Pad12)") (class "Default")
      (node (ref "JP5") (pin "12") (pinfunction "12_12") (pintype "passive"))
    )
    (net (code "101") (name "unconnected-(JP5-Pad13)") (class "Default")
      (node (ref "JP5") (pin "13") (pinfunction "13_13") (pintype "passive"))
    )
    (net (code "102") (name "unconnected-(JP5-Pad14)") (class "Default")
      (node (ref "JP5") (pin "14") (pinfunction "14_14") (pintype "passive"))
    )
    (net (code "103") (name "unconnected-(JP5-Pad15)") (class "Default")
      (node (ref "JP5") (pin "15") (pinfunction "15_15") (pintype "passive"))
    )
    (net (code "104") (name "unconnected-(JP5-Pad16)") (class "Default")
      (node (ref "JP5") (pin "16") (pinfunction "16_16") (pintype "passive"))
    )
    (net (code "105") (name "unconnected-(JP5-Pad17)") (class "Default")
      (node (ref "JP5") (pin "17") (pinfunction "17_17") (pintype "passive"))
    )
    (net (code "106") (name "unconnected-(SV2-Pad2)") (class "Default")
      (node (ref "SV2") (pin "2") (pinfunction "2_2") (pintype "passive"))
    )
    (net (code "107") (name "unconnected-(SV2-Pad5)") (class "Default")
      (node (ref "SV2") (pin "5") (pinfunction "5_5") (pintype "passive"))
    )
    (net (code "108") (name "unconnected-(SV2-Pad7)") (class "Default")
      (node (ref "SV2") (pin "7") (pinfunction "7_7") (pintype "passive"))
    )
    (net (code "109") (name "unconnected-(SV2-Pad8)") (class "Default")
      (node (ref "SV2") (pin "8") (pinfunction "8_8") (pintype "passive"))
    )
    (net (code "110") (name "unconnected-(SV2-Pad9)") (class "Default")
      (node (ref "SV2") (pin "9") (pinfunction "9_9") (pintype "passive"))
    )
  )
)
